# Main.net
KiCad netlist of a schematic drawn in Altium Designer
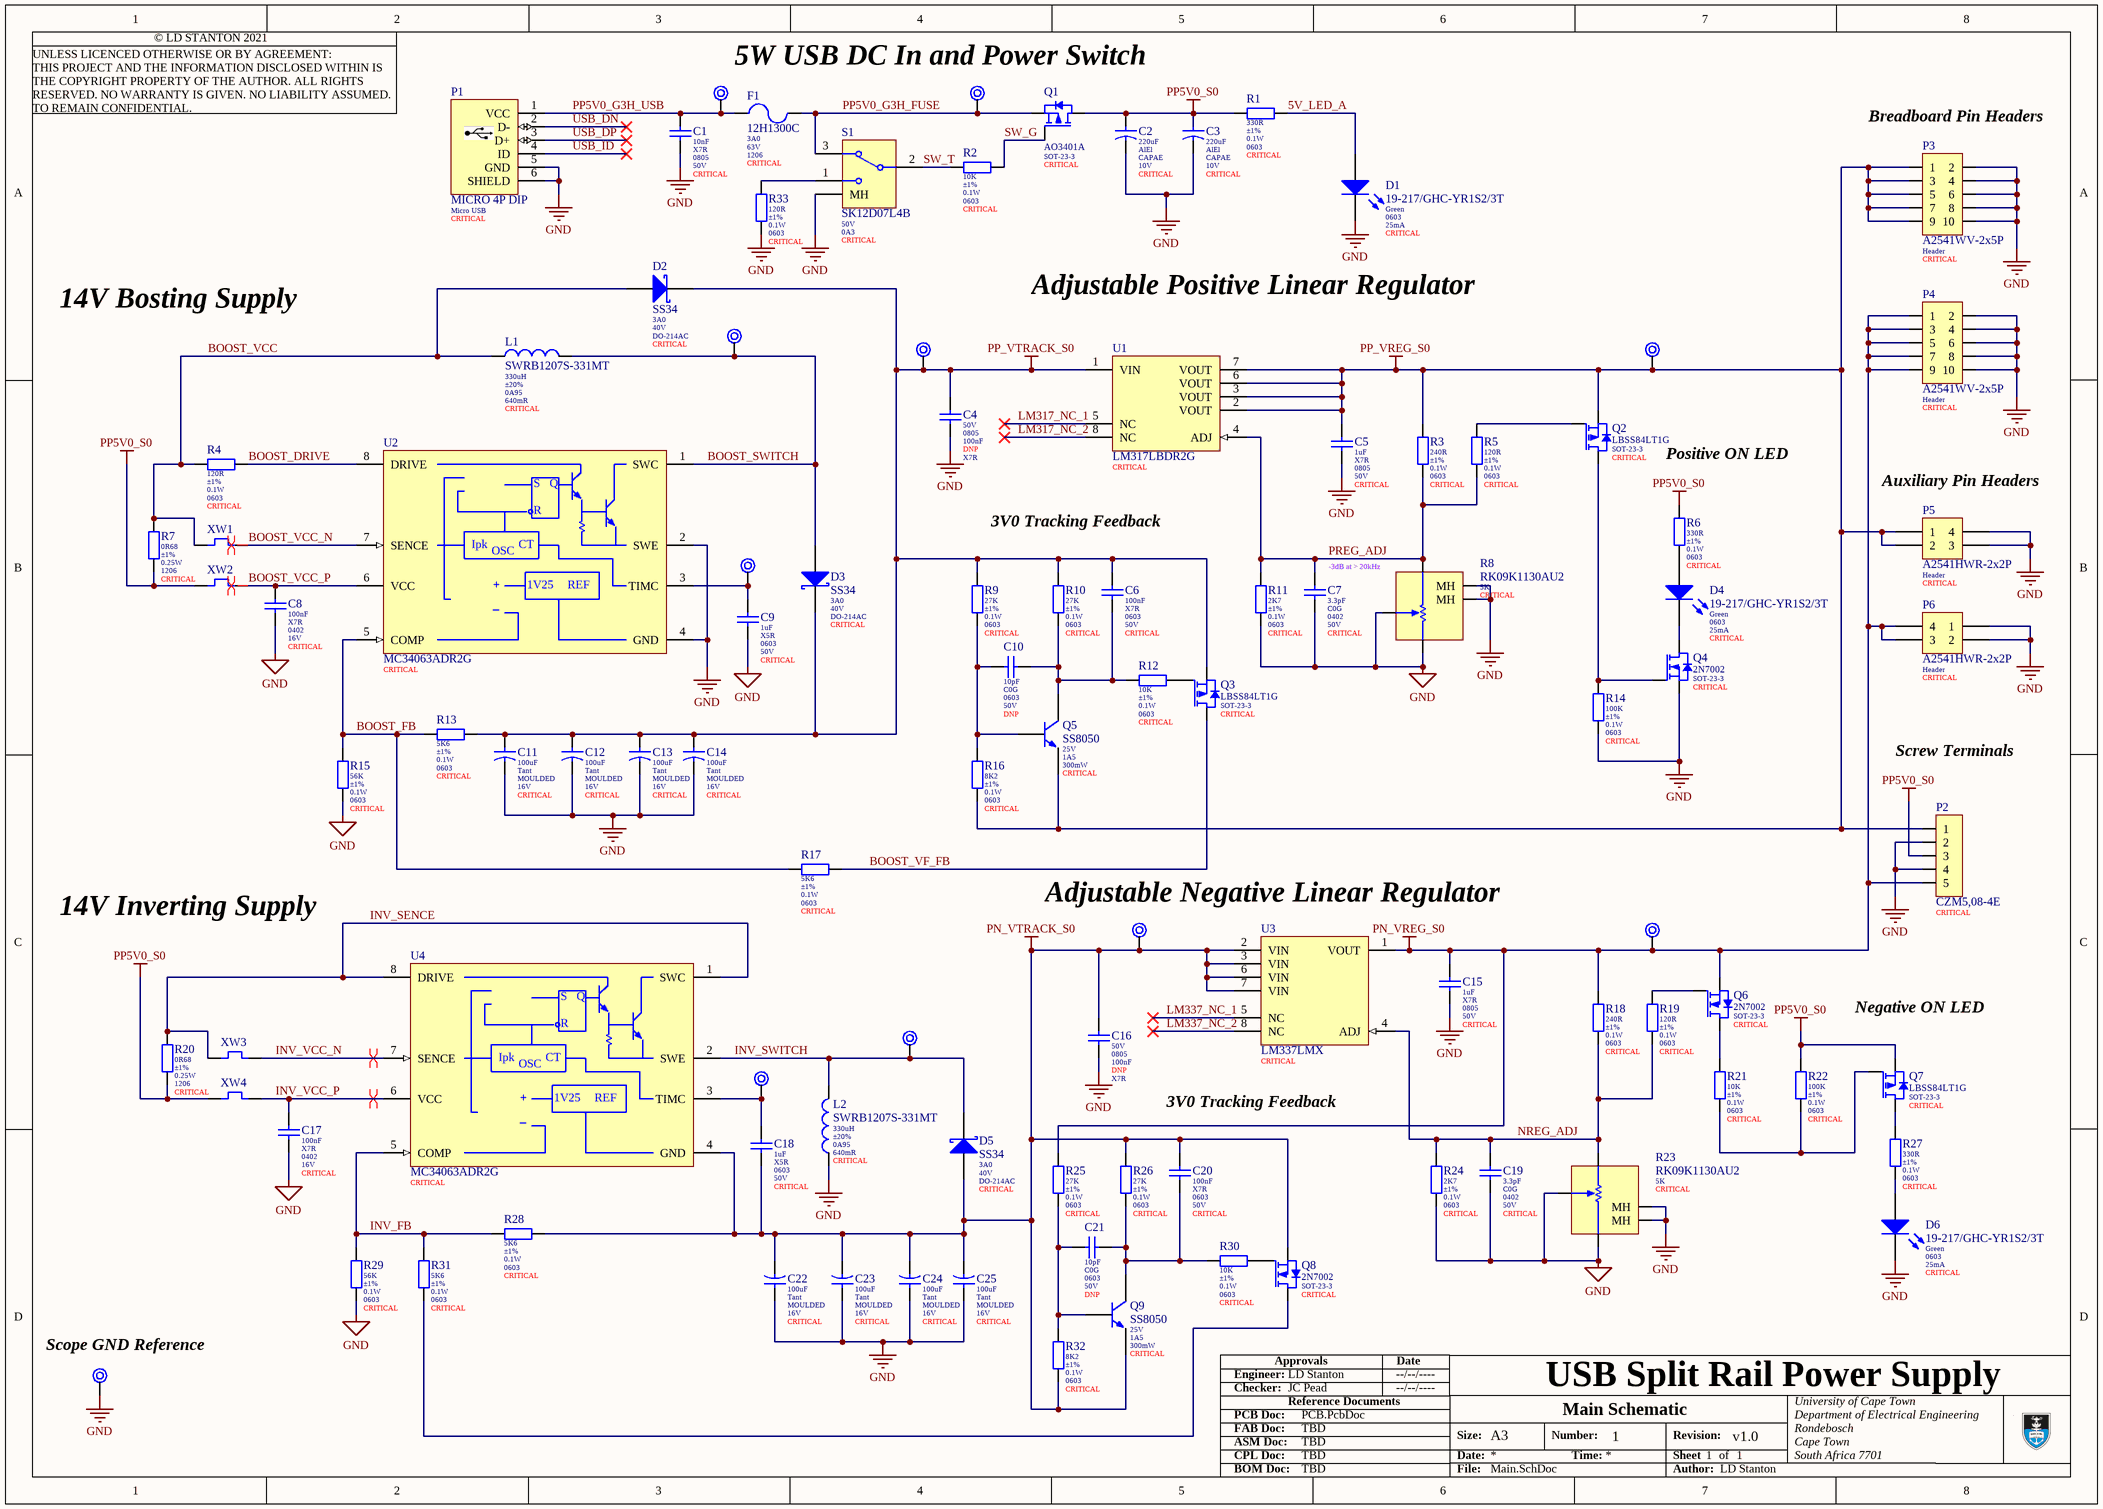
[diagram p0: Main.SchDoc]

(export (version "E")
  (design (tool "Eeschema 10.0.6"))
  (components
    (comp (ref "C1")
      (value "10nF")
      (footprint "0605_065_A_N")
      (description "MLCC 10nF 0805 50V X7R ±10%")
      (fields
        (field (name "TOLERANCE") "±10%")
        (field (name "LCSC PART NUMBER") "C1710")
        (field (name "DIELECTRIC") "X7R")
        (field (name "PACKAGE") "0805")
        (field (name "VOLTAGE") "50V")
        (field (name "POPULATE") "CRITICAL")
      )
      (libsource (lib "Samsung Capacitors") (part "MLCC 10nF 0805 50V X7R"))
    )
    (comp (ref "C2")
      (value "220uF")
      (footprint "CAPAE 6354")
      (description "Aluminium Electrolytic Capacitor 220uF CAPAE 10V ±20%")
      (fields
        (field (name "TOLERANCE") "±20%")
        (field (name "LCSC PART NUMBER") "C3345")
        (field (name "DIELECTRIC") "AlEl")
        (field (name "PACKAGE") "CAPAE")
        (field (name "VOLTAGE") "10V")
        (field (name "POPULATE") "CRITICAL")
      )
      (libsource (lib "JLCPCB Electrolytic Capacitors") (part "Cap AlEl 220uF 10V"))
    )
    (comp (ref "C3")
      (value "220uF")
      (footprint "CAPAE 6354")
      (description "Aluminium Electrolytic Capacitor 220uF CAPAE 10V ±20%")
      (fields
        (field (name "TOLERANCE") "±20%")
        (field (name "LCSC PART NUMBER") "C3345")
        (field (name "DIELECTRIC") "AlEl")
        (field (name "PACKAGE") "CAPAE")
        (field (name "VOLTAGE") "10V")
        (field (name "POPULATE") "CRITICAL")
      )
      (libsource (lib "JLCPCB Electrolytic Capacitors") (part "Cap AlEl 220uF 10V"))
    )
    (comp (ref "C4")
      (value "100nF")
      (footprint "0805")
      (description "MLCC 100nF 50V 0805 X7R ±10%")
      (fields
        (field (name "TOLERANCE") "±10%")
        (field (name "LCSC PART NUMBER") "C49678")
        (field (name "VOLTAGE") "50V")
        (field (name "PACKAGE") "0805")
        (field (name "POPULATE") "DNP")
        (field (name "DIELECTRIC") "X7R")
      )
      (libsource (lib "Yageo Capacitors") (part "MLCC 100nF 50V 0805 X7R"))
    )
    (comp (ref "C5")
      (value "1uF")
      (footprint "0805_125_F_N")
      (description "MLCC 1uF 0805 50V X7R ±10%")
      (fields
        (field (name "TOLERANCE") "±10%")
        (field (name "LCSC PART NUMBER") "C15849")
        (field (name "DIELECTRIC") "X7R")
        (field (name "PACKAGE") "0805")
        (field (name "VOLTAGE") "50V")
        (field (name "POPULATE") "CRITICAL")
      )
      (libsource (lib "Samsung Capacitors") (part "MLCC 1uF 0805 50V X7R"))
    )
    (comp (ref "C6")
      (value "100nF")
      (footprint "0603")
      (description "MLCC 100nF 50V 0603 X7R ±10%")
      (fields
        (field (name "TOLERANCE") "±10%")
        (field (name "LCSC PART NUMBER") "C14663")
        (field (name "DIELECTRIC") "X7R")
        (field (name "PACKAGE") "0603")
        (field (name "VOLTAGE") "50V")
        (field (name "POPULATE") "CRITICAL")
      )
      (libsource (lib "Yageo Capacitors") (part "MLCC 100nF 50V 0603 X7R"))
    )
    (comp (ref "C7")
      (value "3.3pF")
      (footprint "0402_050")
      (description "MLCC 3.3pF 0402 50V C0G ±0.25pF")
      (fields
        (field (name "TOLERANCE") "±0.25pF")
        (field (name "LCSC PART NUMBER") "C1565")
        (field (name "DIELECTRIC") "C0G")
        (field (name "PACKAGE") "0402")
        (field (name "VOLTAGE") "50V")
        (field (name "POPULATE") "CRITICAL")
      )
      (libsource (lib "Guangdong Capacitors") (part "MLCC 3.3pF 0402 50V C0G"))
    )
    (comp (ref "C8")
      (value "100nF")
      (footprint "0402_050_5_N")
      (description "MLCC 100nF 0402 16V X7R ±10%")
      (fields
        (field (name "TOLERANCE") "±10%")
        (field (name "LCSC PART NUMBER") "C1525")
        (field (name "DIELECTRIC") "X7R")
        (field (name "PACKAGE") "0402")
        (field (name "VOLTAGE") "16V")
        (field (name "POPULATE") "CRITICAL")
      )
      (libsource (lib "Samsung Capacitors") (part "MLCC 100nF 0402 16V X7R"))
    )
    (comp (ref "C9")
      (value "1uF")
      (footprint "0603_080_8_N")
      (description "MLCC 1uF 0603 50V X5R ±10%")
      (fields
        (field (name "TOLERANCE") "±10%")
        (field (name "LCSC PART NUMBER") "C15849")
        (field (name "DIELECTRIC") "X5R")
        (field (name "PACKAGE") "0603")
        (field (name "VOLTAGE") "50V")
        (field (name "POPULATE") "CRITICAL")
      )
      (libsource (lib "Samsung Capacitors") (part "MLCC 1uF 0603 50V X5R"))
    )
    (comp (ref "C10")
      (value "10pF")
      (footprint "0603_080_8_N")
      (description "MLCC 10pF 0603 C0G ±0.1pF")
      (fields
        (field (name "TOLERANCE") "±0.1pF")
        (field (name "LCSC PART NUMBER") "C1634")
        (field (name "DIELECTRIC") "C0G")
        (field (name "PACKAGE") "0603")
        (field (name "VOLTAGE") "50V")
        (field (name "POPULATE") "DNP")
      )
      (libsource (lib "Samsung Capacitors") (part "MLCC 10pF 0603 50V C0G"))
    )
    (comp (ref "C11")
      (value "100uF")
      (footprint "Case D")
      (description "Tantalum Capacitor 100uF 16V ±20%")
      (fields
        (field (name "TOLERANCE") "±20%")
        (field (name "LCSC PART NUMBER") "C129696")
        (field (name "DIELECTRIC") "Tant")
        (field (name "PACKAGE") "MOULDED")
        (field (name "VOLTAGE") "16V")
        (field (name "POPULATE") "CRITICAL")
      )
      (libsource (lib "Tantalums Vishay") (part "Cap Tant 100uF 16V"))
    )
    (comp (ref "C12")
      (value "100uF")
      (footprint "Case D")
      (description "Tantalum Capacitor 100uF 16V ±20%")
      (fields
        (field (name "TOLERANCE") "±20%")
        (field (name "LCSC PART NUMBER") "C129696")
        (field (name "DIELECTRIC") "Tant")
        (field (name "PACKAGE") "MOULDED")
        (field (name "VOLTAGE") "16V")
        (field (name "POPULATE") "CRITICAL")
      )
      (libsource (lib "Tantalums Vishay") (part "Cap Tant 100uF 16V"))
    )
    (comp (ref "C13")
      (value "100uF")
      (footprint "Case D")
      (description "Tantalum Capacitor 100uF 16V ±20%")
      (fields
        (field (name "TOLERANCE") "±20%")
        (field (name "LCSC PART NUMBER") "C129696")
        (field (name "DIELECTRIC") "Tant")
        (field (name "PACKAGE") "MOULDED")
        (field (name "VOLTAGE") "16V")
        (field (name "POPULATE") "CRITICAL")
      )
      (libsource (lib "Tantalums Vishay") (part "Cap Tant 100uF 16V"))
    )
    (comp (ref "C14")
      (value "100uF")
      (footprint "Case D")
      (description "Tantalum Capacitor 100uF 16V ±20%")
      (fields
        (field (name "TOLERANCE") "±20%")
        (field (name "LCSC PART NUMBER") "C129696")
        (field (name "DIELECTRIC") "Tant")
        (field (name "PACKAGE") "MOULDED")
        (field (name "VOLTAGE") "16V")
        (field (name "POPULATE") "CRITICAL")
      )
      (libsource (lib "Tantalums Vishay") (part "Cap Tant 100uF 16V"))
    )
    (comp (ref "C15")
      (value "1uF")
      (footprint "0805_125_F_N")
      (description "MLCC 1uF 0805 50V X7R ±10%")
      (fields
        (field (name "TOLERANCE") "±10%")
        (field (name "LCSC PART NUMBER") "C15849")
        (field (name "DIELECTRIC") "X7R")
        (field (name "PACKAGE") "0805")
        (field (name "VOLTAGE") "50V")
        (field (name "POPULATE") "CRITICAL")
      )
      (libsource (lib "Samsung Capacitors") (part "MLCC 1uF 0805 50V X7R"))
    )
    (comp (ref "C16")
      (value "100nF")
      (footprint "0805")
      (description "MLCC 100nF 50V 0805 X7R ±10%")
      (fields
        (field (name "TOLERANCE") "±10%")
        (field (name "LCSC PART NUMBER") "C49678")
        (field (name "VOLTAGE") "50V")
        (field (name "PACKAGE") "0805")
        (field (name "POPULATE") "DNP")
        (field (name "DIELECTRIC") "X7R")
      )
      (libsource (lib "Yageo Capacitors") (part "MLCC 100nF 50V 0805 X7R"))
    )
    (comp (ref "C17")
      (value "100nF")
      (footprint "0402_050_5_N")
      (description "MLCC 100nF 0402 16V X7R ±10%")
      (fields
        (field (name "TOLERANCE") "±10%")
        (field (name "LCSC PART NUMBER") "C1525")
        (field (name "DIELECTRIC") "X7R")
        (field (name "PACKAGE") "0402")
        (field (name "VOLTAGE") "16V")
        (field (name "POPULATE") "CRITICAL")
      )
      (libsource (lib "Samsung Capacitors") (part "MLCC 100nF 0402 16V X7R"))
    )
    (comp (ref "C18")
      (value "1uF")
      (footprint "0603_080_8_N")
      (description "MLCC 1uF 0603 50V X5R ±10%")
      (fields
        (field (name "TOLERANCE") "±10%")
        (field (name "LCSC PART NUMBER") "C15849")
        (field (name "DIELECTRIC") "X5R")
        (field (name "PACKAGE") "0603")
        (field (name "VOLTAGE") "50V")
        (field (name "POPULATE") "CRITICAL")
      )
      (libsource (lib "Samsung Capacitors") (part "MLCC 1uF 0603 50V X5R"))
    )
    (comp (ref "C19")
      (value "3.3pF")
      (footprint "0402_050")
      (description "MLCC 3.3pF 0402 50V C0G ±0.25pF")
      (fields
        (field (name "TOLERANCE") "±0.25pF")
        (field (name "LCSC PART NUMBER") "C1565")
        (field (name "DIELECTRIC") "C0G")
        (field (name "PACKAGE") "0402")
        (field (name "VOLTAGE") "50V")
        (field (name "POPULATE") "CRITICAL")
      )
      (libsource (lib "Guangdong Capacitors") (part "MLCC 3.3pF 0402 50V C0G"))
    )
    (comp (ref "C20")
      (value "100nF")
      (footprint "0603")
      (description "MLCC 100nF 50V 0603 X7R ±10%")
      (fields
        (field (name "TOLERANCE") "±10%")
        (field (name "LCSC PART NUMBER") "C14663")
        (field (name "DIELECTRIC") "X7R")
        (field (name "PACKAGE") "0603")
        (field (name "VOLTAGE") "50V")
        (field (name "POPULATE") "CRITICAL")
      )
      (libsource (lib "Yageo Capacitors") (part "MLCC 100nF 50V 0603 X7R"))
    )
    (comp (ref "C21")
      (value "10pF")
      (footprint "0603_080_8_N")
      (description "MLCC 10pF 0603 C0G ±0.1pF")
      (fields
        (field (name "TOLERANCE") "±0.1pF")
        (field (name "LCSC PART NUMBER") "C1634")
        (field (name "DIELECTRIC") "C0G")
        (field (name "PACKAGE") "0603")
        (field (name "VOLTAGE") "50V")
        (field (name "POPULATE") "DNP")
      )
      (libsource (lib "Samsung Capacitors") (part "MLCC 10pF 0603 50V C0G"))
    )
    (comp (ref "C22")
      (value "100uF")
      (footprint "Case D")
      (description "Tantalum Capacitor 100uF 16V ±20%")
      (fields
        (field (name "TOLERANCE") "±20%")
        (field (name "LCSC PART NUMBER") "C129696")
        (field (name "DIELECTRIC") "Tant")
        (field (name "PACKAGE") "MOULDED")
        (field (name "VOLTAGE") "16V")
        (field (name "POPULATE") "CRITICAL")
      )
      (libsource (lib "Tantalums Vishay") (part "Cap Tant 100uF 16V"))
    )
    (comp (ref "C23")
      (value "100uF")
      (footprint "Case D")
      (description "Tantalum Capacitor 100uF 16V ±20%")
      (fields
        (field (name "TOLERANCE") "±20%")
        (field (name "LCSC PART NUMBER") "C129696")
        (field (name "DIELECTRIC") "Tant")
        (field (name "PACKAGE") "MOULDED")
        (field (name "VOLTAGE") "16V")
        (field (name "POPULATE") "CRITICAL")
      )
      (libsource (lib "Tantalums Vishay") (part "Cap Tant 100uF 16V"))
    )
    (comp (ref "C24")
      (value "100uF")
      (footprint "Case D")
      (description "Tantalum Capacitor 100uF 16V ±20%")
      (fields
        (field (name "TOLERANCE") "±20%")
        (field (name "LCSC PART NUMBER") "C129696")
        (field (name "DIELECTRIC") "Tant")
        (field (name "PACKAGE") "MOULDED")
        (field (name "VOLTAGE") "16V")
        (field (name "POPULATE") "CRITICAL")
      )
      (libsource (lib "Tantalums Vishay") (part "Cap Tant 100uF 16V"))
    )
    (comp (ref "C25")
      (value "100uF")
      (footprint "Case D")
      (description "Tantalum Capacitor 100uF 16V ±20%")
      (fields
        (field (name "TOLERANCE") "±20%")
        (field (name "LCSC PART NUMBER") "C129696")
        (field (name "DIELECTRIC") "Tant")
        (field (name "PACKAGE") "MOULDED")
        (field (name "VOLTAGE") "16V")
        (field (name "POPULATE") "CRITICAL")
      )
      (libsource (lib "Tantalums Vishay") (part "Cap Tant 100uF 16V"))
    )
    (comp (ref "D1")
      (value "19-217/GHC-YR1S2/3T")
      (footprint "LED 0603")
      (description "LED 0603 SMT Green")
      (fields
        (field (name "LCSC PART NUMBER") "C72043")
        (field (name "COLOUR") "Green")
        (field (name "PACKAGE") "0603")
        (field (name "CURRENT") "25mA")
        (field (name "PLACEMENT") "CRITICAL")
      )
      (libsource (lib "JLCPCB LEDs") (part "LED 0603 Green"))
    )
    (comp (ref "D2")
      (value "SS34")
      (footprint "DO-214AC")
      (description "Schottky Barrier Diode 40V 3A0 550mV")
      (fields
        (field (name "LCSC PART NUMBER") "C8678")
        (field (name "MANUFACTURER") "MDD")
        (field (name "DC FORWARD CURENT") "3A0")
        (field (name "DC REVERSE BLOCKING") "40V")
        (field (name "PACKAGE") "DO-214AC")
        (field (name "PLACEMENT") "CRITICAL")
      )
      (libsource (lib "Schottky Barrier Diodes") (part "SS34"))
    )
    (comp (ref "D3")
      (value "SS34")
      (footprint "DO-214AC")
      (description "Schottky Barrier Diode 40V 3A0 550mV")
      (fields
        (field (name "LCSC PART NUMBER") "C8678")
        (field (name "MANUFACTURER") "MDD")
        (field (name "DC FORWARD CURENT") "3A0")
        (field (name "DC REVERSE BLOCKING") "40V")
        (field (name "PACKAGE") "DO-214AC")
        (field (name "PLACEMENT") "CRITICAL")
      )
      (libsource (lib "Schottky Barrier Diodes") (part "SS34"))
    )
    (comp (ref "D4")
      (value "19-217/GHC-YR1S2/3T")
      (footprint "LED 0603")
      (description "LED 0603 SMT Green")
      (fields
        (field (name "LCSC PART NUMBER") "C72043")
        (field (name "COLOUR") "Green")
        (field (name "PACKAGE") "0603")
        (field (name "CURRENT") "25mA")
        (field (name "PLACEMENT") "CRITICAL")
      )
      (libsource (lib "JLCPCB LEDs") (part "LED 0603 Green"))
    )
    (comp (ref "D5")
      (value "SS34")
      (footprint "DO-214AC")
      (description "Schottky Barrier Diode 40V 3A0 550mV")
      (fields
        (field (name "LCSC PART NUMBER") "C8678")
        (field (name "MANUFACTURER") "MDD")
        (field (name "DC FORWARD CURENT") "3A0")
        (field (name "DC REVERSE BLOCKING") "40V")
        (field (name "PACKAGE") "DO-214AC")
        (field (name "PLACEMENT") "CRITICAL")
      )
      (libsource (lib "Schottky Barrier Diodes") (part "SS34"))
    )
    (comp (ref "D6")
      (value "19-217/GHC-YR1S2/3T")
      (footprint "LED 0603")
      (description "LED 0603 SMT Green")
      (fields
        (field (name "LCSC PART NUMBER") "C72043")
        (field (name "COLOUR") "Green")
        (field (name "PACKAGE") "0603")
        (field (name "CURRENT") "25mA")
        (field (name "PLACEMENT") "CRITICAL")
      )
      (libsource (lib "JLCPCB LEDs") (part "LED 0603 Green"))
    )
    (comp (ref "F1")
      (value "12H1300C")
      (footprint "1206_060")
      (description "Fuse SMD Slow Blow 3A 63VAC 1206")
      (fields
        (field (name "LCSC PART NUMBER") "C182445")
        (field (name "CURRENT") "3A0")
        (field (name "VOLTAGE") "63V")
        (field (name "PACKAGE") "1206")
        (field (name "PLACEMENT") "CRITICAL")
      )
      (libsource (lib "Fuses") (part "Fuse 3A Slow 1206"))
    )
    (comp (ref "L1")
      (value "SWRB1207S-331MT")
      (footprint "SWRB1207S")
      (description "Inductor 330uH ±20% 0A95 640mR Moulded SMD 12.5x12.5x8.0mm")
      (fields
        (field (name "LCSC PART NUMBER") "C169381")
        (field (name "MANUFACTURER") "Sunlord")
        (field (name "ALTIUM_VALUE") "330uH")
        (field (name "TOLERANCE") "±20%")
        (field (name "RATED CURRENT") "0A95")
        (field (name "DC RESISTANCE") "640mR")
        (field (name "POPULATE") "CRITICAL")
      )
      (libsource (lib "JLCPCB Inductors") (part "Inductor 330uH ±20% 0A95"))
    )
    (comp (ref "L2")
      (value "SWRB1207S-331MT")
      (footprint "SWRB1207S")
      (description "Inductor 330uH ±20% 0A95 640mR Moulded SMD 12.5x12.5x8.0mm")
      (fields
        (field (name "LCSC PART NUMBER") "C169381")
        (field (name "MANUFACTURER") "Sunlord")
        (field (name "ALTIUM_VALUE") "330uH")
        (field (name "TOLERANCE") "±20%")
        (field (name "RATED CURRENT") "0A95")
        (field (name "DC RESISTANCE") "640mR")
        (field (name "POPULATE") "CRITICAL")
      )
      (libsource (lib "JLCPCB Inductors") (part "Inductor 330uH ±20% 0A95"))
    )
    (comp (ref "P1")
      (value "MICRO 4P DIP")
      (footprint "MICRO 4P DIP")
      (description "Micro USB Connector SMT with TH Mounts")
      (fields
        (field (name "LCSC PART NUMBER") "C456008")
        (field (name "USB CONNECTOR TYPE") "Micro USB")
        (field (name "PLACEMENT") "CRITICAL")
      )
      (libsource (lib "USB Connectors") (part "MICRO 4P DIP"))
    )
    (comp (ref "P2")
      (value "CZM5,08-4E")
      (footprint "Screw Down 5")
      (description "Screw Down Terminal 5 Way 5.08mm Pitch")
      (fields (field (name "PLACEMENT") "CRITICAL"))
      (libsource (lib "Connectors") (part "Screw Down 5 Way 5.08mm"))
    )
    (comp (ref "P3")
      (value "A2541WV-2x5P")
      (footprint "Pin Header 10 2 Vertical Male")
      (description "Pin Header 10 Way Double Row Vertical Angle")
      (fields
        (field (name "TYPE") "Header")
        (field (name "PLACEMENT") "CRITICAL")
        (field (name "LCSC PART NUMBER") "C225520")
      )
      (libsource (lib "JLCPCB Pin Headers") (part "Pin Header 10 2 Male Vertical"))
    )
    (comp (ref "P4")
      (value "A2541WV-2x5P")
      (footprint "Pin Header 10 2 Vertical Male")
      (description "Pin Header 10 Way Double Row Vertical Angle")
      (fields
        (field (name "TYPE") "Header")
        (field (name "PLACEMENT") "CRITICAL")
        (field (name "LCSC PART NUMBER") "C225520")
      )
      (libsource (lib "JLCPCB Pin Headers") (part "Pin Header 10 2 Male Vertical"))
    )
    (comp (ref "P5")
      (value "A2541HWR-2x2P")
      (footprint "Pin Header 4 2 Right Female")
      (description "Pin Header 4 Way Double Row Female Right Angle")
      (fields (field (name "TYPE") "Header") (field (name "PLACEMENT") "CRITICAL"))
      (libsource (lib "") (part "Pin Header 4 2 Female Right_1"))
    )
    (comp (ref "P6")
      (value "A2541HWR-2x2P")
      (footprint "Pin Header 4 2 Right Female")
      (description "Pin Header 4 Way Double Row Female Right Angle")
      (fields (field (name "TYPE") "Header") (field (name "PLACEMENT") "CRITICAL"))
      (libsource (lib "JLCPCB Pin Headers") (part "Pin Header 4 2 Female Right"))
    )
    (comp (ref "Q1")
      (value "AO3401A")
      (footprint "SOT-23-3 (2N7002)")
      (description "MOSFET Trench 4A0 30V 85mR ±12V P-Channel Enhancement AOS SOT-22-3L")
      (fields
        (field (name "POWER") "0.9W")
        (field (name "LCSC PART NUMBER") "C20917")
        (field (name "PACKAGE") "SOT-23-3")
        (field (name "PLACEMENT") "CRITICAL")
      )
      (libsource (lib "JLCPCB Transistors") (part "AO3401A"))
    )
    (comp (ref "Q2")
      (value "LBSS84LT1G")
      (footprint "SOT-23-3 (2N7002)")
      (description "Small Signal MOSFET, 130 mA, 50 V, P-Channel, Enhancement, LRC SOT-23-3")
      (fields
        (field (name "POWER") "0.225W")
        (field (name "LCSC PART NUMBER") "C8492")
        (field (name "PACKAGE") "SOT-23-3")
        (field (name "PLACEMENT") "CRITICAL")
      )
      (libsource (lib "JLCPCB Transistors") (part "LBSS84LT1G"))
    )
    (comp (ref "Q3")
      (value "LBSS84LT1G")
      (footprint "SOT-23-3 (2N7002)")
      (description "Small Signal MOSFET, 130 mA, 50 V, P-Channel, Enhancement, LRC SOT-23-3")
      (fields
        (field (name "POWER") "0.225W")
        (field (name "LCSC PART NUMBER") "C8492")
        (field (name "PACKAGE") "SOT-23-3")
        (field (name "PLACEMENT") "CRITICAL")
      )
      (libsource (lib "JLCPCB Transistors") (part "LBSS84LT1G"))
    )
    (comp (ref "Q4")
      (value "2N7002")
      (footprint "SOT-23-3 (2N7002)")
      (description "Small Signal MOSFET, 500 mA, 60 V, N-Channel, Enhancement, JCET SOT-23-3")
      (fields
        (field (name "POWER") "0.225W")
        (field (name "LCSC PART NUMBER") "C8545")
        (field (name "PACKAGE") "SOT-23-3")
        (field (name "PLACEMENT") "CRITICAL")
      )
      (libsource (lib "JLCPCB Transistors") (part "2N7002"))
    )
    (comp (ref "Q5")
      (value "SS8050")
      (footprint "SOT-23-3 Generic")
      (description "BJT NPN 1A5 25V SOT-23-3")
      (fields
        (field (name "MANUFACTURER") "Changjiang Electronics")
        (field (name "LCSC PART NUMBER") "C2150")
        (field (name "VCE") "25V")
        (field (name "COLLECTOR CURRENT") "1A5")
        (field (name "POWER") "300mW")
        (field (name "PLACEMENT") "CRITICAL")
      )
      (libsource (lib "JLCPCB Transistors") (part "SS8050"))
    )
    (comp (ref "Q6")
      (value "2N7002")
      (footprint "SOT-23-3 (2N7002)")
      (description "Small Signal MOSFET, 500 mA, 60 V, N-Channel, Enhancement, JCET SOT-23-3")
      (fields
        (field (name "POWER") "0.225W")
        (field (name "LCSC PART NUMBER") "C8545")
        (field (name "PACKAGE") "SOT-23-3")
        (field (name "PLACEMENT") "CRITICAL")
      )
      (libsource (lib "JLCPCB Transistors") (part "2N7002"))
    )
    (comp (ref "Q7")
      (value "LBSS84LT1G")
      (footprint "SOT-23-3 (2N7002)")
      (description "Small Signal MOSFET, 130 mA, 50 V, P-Channel, Enhancement, LRC SOT-23-3")
      (fields
        (field (name "POWER") "0.225W")
        (field (name "LCSC PART NUMBER") "C8492")
        (field (name "PACKAGE") "SOT-23-3")
        (field (name "PLACEMENT") "CRITICAL")
      )
      (libsource (lib "JLCPCB Transistors") (part "LBSS84LT1G"))
    )
    (comp (ref "Q8")
      (value "2N7002")
      (footprint "SOT-23-3 (2N7002)")
      (description "Small Signal MOSFET, 500 mA, 60 V, N-Channel, Enhancement, JCET SOT-23-3")
      (fields
        (field (name "POWER") "0.225W")
        (field (name "LCSC PART NUMBER") "C8545")
        (field (name "PACKAGE") "SOT-23-3")
        (field (name "PLACEMENT") "CRITICAL")
      )
      (libsource (lib "JLCPCB Transistors") (part "2N7002"))
    )
    (comp (ref "Q9")
      (value "SS8050")
      (footprint "SOT-23-3 Generic")
      (description "BJT NPN 1A5 25V SOT-23-3")
      (fields
        (field (name "MANUFACTURER") "Changjiang Electronics")
        (field (name "LCSC PART NUMBER") "C2150")
        (field (name "VCE") "25V")
        (field (name "COLLECTOR CURRENT") "1A5")
        (field (name "POWER") "300mW")
        (field (name "PLACEMENT") "CRITICAL")
      )
      (libsource (lib "JLCPCB Transistors") (part "SS8050"))
    )
    (comp (ref "R1")
      (value "330R")
      (footprint "0603")
      (description "Lead Free Thick Film Chip Resistor 0805 ±1%")
      (fields
        (field (name "LCSC PART NUMBER") "C23138")
        (field (name "TOLERANCE") "±1%")
        (field (name "POWER") "0.1W")
        (field (name "PACKAGE") "0603")
        (field (name "POPULATE") "CRITICAL")
        (field (name "Comment") "0603WAF3300T5E")
      )
      (libsource (lib "Uniroyal Resistors") (part "Res 330R 0603"))
    )
    (comp (ref "R2")
      (value "10K")
      (footprint "0603")
      (description "Lead Free Thick Film Chip Resistor 0603 ±1%")
      (fields
        (field (name "LCSC PART NUMBER") "C25804")
        (field (name "TOLERANCE") "±1%")
        (field (name "POWER") "0.1W")
        (field (name "PACKAGE") "0603")
        (field (name "POPULATE") "CRITICAL")
        (field (name "Comment") "0603WAF1002T5E")
      )
      (libsource (lib "Uniroyal Resistors") (part "Res 10K 0603"))
    )
    (comp (ref "R3")
      (value "240R")
      (footprint "0603")
      (description "Lead Free Thick Film Chip Resistor 0603 ±1%")
      (fields
        (field (name "LCSC PART NUMBER") "C23350")
        (field (name "TOLERANCE") "±1%")
        (field (name "POWER") "0.1W")
        (field (name "PACKAGE") "0603")
        (field (name "POPULATE") "CRITICAL")
        (field (name "Comment") "0603WAF2400T5E")
      )
      (libsource (lib "Uniroyal Resistors") (part "Res 240R 0603"))
    )
    (comp (ref "R4")
      (value "120R")
      (footprint "0603")
      (description "Lead Free Thick Film Chip Resistor 0603 ±1%")
      (fields
        (field (name "LCSC PART NUMBER") "C22787")
        (field (name "TOLERANCE") "±1%")
        (field (name "POWER") "0.1W")
        (field (name "PACKAGE") "0603")
        (field (name "POPULATE") "CRITICAL")
        (field (name "Comment") "0603WAF1200T5E")
      )
      (libsource (lib "Uniroyal Resistors") (part "Res 120R 0603"))
    )
    (comp (ref "R5")
      (value "120R")
      (footprint "0603")
      (description "Lead Free Thick Film Chip Resistor 0603 ±1%")
      (fields
        (field (name "LCSC PART NUMBER") "C22787")
        (field (name "TOLERANCE") "±1%")
        (field (name "POWER") "0.1W")
        (field (name "PACKAGE") "0603")
        (field (name "POPULATE") "CRITICAL")
        (field (name "Comment") "0603WAF1200T5E")
      )
      (libsource (lib "Uniroyal Resistors") (part "Res 120R 0603"))
    )
    (comp (ref "R6")
      (value "330R")
      (footprint "0603")
      (description "Lead Free Thick Film Chip Resistor 0805 ±1%")
      (fields
        (field (name "LCSC PART NUMBER") "C23138")
        (field (name "TOLERANCE") "±1%")
        (field (name "POWER") "0.1W")
        (field (name "PACKAGE") "0603")
        (field (name "POPULATE") "CRITICAL")
        (field (name "Comment") "0603WAF3300T5E")
      )
      (libsource (lib "Uniroyal Resistors") (part "Res 330R 0603"))
    )
    (comp (ref "R7")
      (value "0R68")
      (footprint "1206")
      (description "Lead Free Thick Film Chip Resistor 1206 ±1%")
      (fields
        (field (name "LCSC PART NUMBER") "C19108")
        (field (name "TOLERANCE") "±1%")
        (field (name "POWER") "0.25W")
        (field (name "PACKAGE") "1206")
        (field (name "POPULATE") "CRITICAL")
        (field (name "Comment") "1206W4F680LT5E")
      )
      (libsource (lib "Uniroyal Resistors") (part "Res 0R68 1206"))
    )
    (comp (ref "R8")
      (value "RK09K1130AU2")
      (footprint "RK09K113")
      (description "5K Potentiometer THT 9.8mm Diameter ±20% 20VDC")
      (fields
        (field (name "MANUFACTURER") "Alpsalpine")
        (field (name "RESISTANCE") "5K")
        (field (name "PLACEMENT") "CRITICAL")
        (field (name "LCSC PART NUMBER") "C388855")
      )
      (libsource (lib "Potentiometers") (part "Pot 5K THT 9.8mm"))
    )
    (comp (ref "R9")
      (value "27K")
      (footprint "0603")
      (description "Lead Free Thick Film Chip Resistor 0603 ±1%")
      (fields
        (field (name "LCSC PART NUMBER") "C22967")
        (field (name "TOLERANCE") "±1%")
        (field (name "POWER") "0.1W")
        (field (name "PACKAGE") "0603")
        (field (name "POPULATE") "CRITICAL")
        (field (name "Comment") "0603WAF2702T5E")
      )
      (libsource (lib "Uniroyal Resistors") (part "Res 27K 0603"))
    )
    (comp (ref "R10")
      (value "27K")
      (footprint "0603")
      (description "Lead Free Thick Film Chip Resistor 0603 ±1%")
      (fields
        (field (name "LCSC PART NUMBER") "C22967")
        (field (name "TOLERANCE") "±1%")
        (field (name "POWER") "0.1W")
        (field (name "PACKAGE") "0603")
        (field (name "POPULATE") "CRITICAL")
        (field (name "Comment") "0603WAF2702T5E")
      )
      (libsource (lib "Uniroyal Resistors") (part "Res 27K 0603"))
    )
    (comp (ref "R11")
      (value "2K7")
      (footprint "0603")
      (description "Lead Free Thick Film Chip Resistor 0603 ±1%")
      (fields
        (field (name "LCSC PART NUMBER") "C13167")
        (field (name "TOLERANCE") "±1%")
        (field (name "POWER") "0.1W")
        (field (name "PACKAGE") "0603")
        (field (name "POPULATE") "CRITICAL")
        (field (name "Comment") "0603WAF2701T5E")
      )
      (libsource (lib "Uniroyal Resistors") (part "Res 2K7 0603"))
    )
    (comp (ref "R12")
      (value "10K")
      (footprint "0603")
      (description "Lead Free Thick Film Chip Resistor 0603 ±1%")
      (fields
        (field (name "LCSC PART NUMBER") "C25804")
        (field (name "TOLERANCE") "±1%")
        (field (name "POWER") "0.1W")
        (field (name "PACKAGE") "0603")
        (field (name "POPULATE") "CRITICAL")
        (field (name "Comment") "0603WAF1002T5E")
      )
      (libsource (lib "Uniroyal Resistors") (part "Res 10K 0603"))
    )
    (comp (ref "R13")
      (value "5K6")
      (footprint "0603")
      (description "Lead Free Thick Film Chip Resistor 0603 ±1%")
      (fields
        (field (name "LCSC PART NUMBER") "C23189")
        (field (name "TOLERANCE") "±1%")
        (field (name "POWER") "0.1W")
        (field (name "PACKAGE") "0603")
        (field (name "POPULATE") "CRITICAL")
        (field (name "Comment") "0603WAF5601T5E")
      )
      (libsource (lib "Uniroyal Resistors") (part "Res 5K6 0603"))
    )
    (comp (ref "R14")
      (value "100K")
      (footprint "0603")
      (description "Lead Free Thick Film Chip Resistor 0603 ±1%")
      (fields
        (field (name "LCSC PART NUMBER") "C25803")
        (field (name "TOLERANCE") "±1%")
        (field (name "POWER") "0.1W")
        (field (name "PACKAGE") "0603")
        (field (name "POPULATE") "CRITICAL")
        (field (name "Comment") "0603WAF1003T5E")
      )
      (libsource (lib "Uniroyal Resistors") (part "Res 100K 0603"))
    )
    (comp (ref "R15")
      (value "56K")
      (footprint "0603")
      (description "Lead Free Thick Film Chip Resistor 0603 ±1%")
      (fields
        (field (name "LCSC PART NUMBER") "C23206")
        (field (name "TOLERANCE") "±1%")
        (field (name "POWER") "0.1W")
        (field (name "PACKAGE") "0603")
        (field (name "POPULATE") "CRITICAL")
        (field (name "Comment") "0603WAF5602T5E")
      )
      (libsource (lib "Uniroyal Resistors") (part "Res 56K 0603"))
    )
    (comp (ref "R16")
      (value "8K2")
      (footprint "0603")
      (description "Lead Free Thick Film Chip Resistor 0603 ±1%")
      (fields
        (field (name "LCSC PART NUMBER") "C25981")
        (field (name "TOLERANCE") "±1%")
        (field (name "POWER") "0.1W")
        (field (name "PACKAGE") "0603")
        (field (name "POPULATE") "CRITICAL")
        (field (name "Comment") "0603WAF8201T5E")
      )
      (libsource (lib "Uniroyal Resistors") (part "Res 8K2 0603"))
    )
    (comp (ref "R17")
      (value "5K6")
      (footprint "0603")
      (description "Lead Free Thick Film Chip Resistor 0603 ±1%")
      (fields
        (field (name "LCSC PART NUMBER") "C23189")
        (field (name "TOLERANCE") "±1%")
        (field (name "POWER") "0.1W")
        (field (name "PACKAGE") "0603")
        (field (name "POPULATE") "CRITICAL")
        (field (name "Comment") "0603WAF5601T5E")
      )
      (libsource (lib "Uniroyal Resistors") (part "Res 5K6 0603"))
    )
    (comp (ref "R18")
      (value "240R")
      (footprint "0603")
      (description "Lead Free Thick Film Chip Resistor 0603 ±1%")
      (fields
        (field (name "LCSC PART NUMBER") "C23350")
        (field (name "TOLERANCE") "±1%")
        (field (name "POWER") "0.1W")
        (field (name "PACKAGE") "0603")
        (field (name "POPULATE") "CRITICAL")
        (field (name "Comment") "0603WAF2400T5E")
      )
      (libsource (lib "Uniroyal Resistors") (part "Res 240R 0603"))
    )
    (comp (ref "R19")
      (value "120R")
      (footprint "0603")
      (description "Lead Free Thick Film Chip Resistor 0603 ±1%")
      (fields
        (field (name "LCSC PART NUMBER") "C22787")
        (field (name "TOLERANCE") "±1%")
        (field (name "POWER") "0.1W")
        (field (name "PACKAGE") "0603")
        (field (name "POPULATE") "CRITICAL")
        (field (name "Comment") "0603WAF1200T5E")
      )
      (libsource (lib "Uniroyal Resistors") (part "Res 120R 0603"))
    )
    (comp (ref "R20")
      (value "0R68")
      (footprint "1206")
      (description "Lead Free Thick Film Chip Resistor 1206 ±1%")
      (fields
        (field (name "LCSC PART NUMBER") "C19108")
        (field (name "TOLERANCE") "±1%")
        (field (name "POWER") "0.25W")
        (field (name "PACKAGE") "1206")
        (field (name "POPULATE") "CRITICAL")
        (field (name "Comment") "1206W4F680LT5E")
      )
      (libsource (lib "Uniroyal Resistors") (part "Res 0R68 1206"))
    )
    (comp (ref "R21")
      (value "10K")
      (footprint "0603")
      (description "Lead Free Thick Film Chip Resistor 0603 ±1%")
      (fields
        (field (name "LCSC PART NUMBER") "C25804")
        (field (name "TOLERANCE") "±1%")
        (field (name "POWER") "0.1W")
        (field (name "PACKAGE") "0603")
        (field (name "POPULATE") "CRITICAL")
        (field (name "Comment") "0603WAF1002T5E")
      )
      (libsource (lib "Uniroyal Resistors") (part "Res 10K 0603"))
    )
    (comp (ref "R22")
      (value "100K")
      (footprint "0603")
      (description "Lead Free Thick Film Chip Resistor 0603 ±1%")
      (fields
        (field (name "LCSC PART NUMBER") "C25803")
        (field (name "TOLERANCE") "±1%")
        (field (name "POWER") "0.1W")
        (field (name "PACKAGE") "0603")
        (field (name "POPULATE") "CRITICAL")
        (field (name "Comment") "0603WAF1003T5E")
      )
      (libsource (lib "Uniroyal Resistors") (part "Res 100K 0603"))
    )
    (comp (ref "R23")
      (value "RK09K1130AU2")
      (footprint "RK09K113")
      (description "5K Potentiometer THT 9.8mm Diameter ±20% 20VDC")
      (fields
        (field (name "MANUFACTURER") "Alpsalpine")
        (field (name "RESISTANCE") "5K")
        (field (name "PLACEMENT") "CRITICAL")
        (field (name "LCSC PART NUMBER") "C388855")
      )
      (libsource (lib "") (part "Pot 5K THT 9.8mm_1"))
    )
    (comp (ref "R24")
      (value "2K7")
      (footprint "0603")
      (description "Lead Free Thick Film Chip Resistor 0603 ±1%")
      (fields
        (field (name "LCSC PART NUMBER") "C13167")
        (field (name "TOLERANCE") "±1%")
        (field (name "POWER") "0.1W")
        (field (name "PACKAGE") "0603")
        (field (name "POPULATE") "CRITICAL")
        (field (name "Comment") "0603WAF2701T5E")
      )
      (libsource (lib "Uniroyal Resistors") (part "Res 2K7 0603"))
    )
    (comp (ref "R25")
      (value "27K")
      (footprint "0603")
      (description "Lead Free Thick Film Chip Resistor 0603 ±1%")
      (fields
        (field (name "LCSC PART NUMBER") "C22967")
        (field (name "TOLERANCE") "±1%")
        (field (name "POWER") "0.1W")
        (field (name "PACKAGE") "0603")
        (field (name "POPULATE") "CRITICAL")
        (field (name "Comment") "0603WAF2702T5E")
      )
      (libsource (lib "Uniroyal Resistors") (part "Res 27K 0603"))
    )
    (comp (ref "R26")
      (value "27K")
      (footprint "0603")
      (description "Lead Free Thick Film Chip Resistor 0603 ±1%")
      (fields
        (field (name "LCSC PART NUMBER") "C22967")
        (field (name "TOLERANCE") "±1%")
        (field (name "POWER") "0.1W")
        (field (name "PACKAGE") "0603")
        (field (name "POPULATE") "CRITICAL")
        (field (name "Comment") "0603WAF2702T5E")
      )
      (libsource (lib "Uniroyal Resistors") (part "Res 27K 0603"))
    )
    (comp (ref "R27")
      (value "330R")
      (footprint "0603")
      (description "Lead Free Thick Film Chip Resistor 0805 ±1%")
      (fields
        (field (name "LCSC PART NUMBER") "C23138")
        (field (name "TOLERANCE") "±1%")
        (field (name "POWER") "0.1W")
        (field (name "PACKAGE") "0603")
        (field (name "POPULATE") "CRITICAL")
        (field (name "Comment") "0603WAF3300T5E")
      )
      (libsource (lib "Uniroyal Resistors") (part "Res 330R 0603"))
    )
    (comp (ref "R28")
      (value "5K6")
      (footprint "0603")
      (description "Lead Free Thick Film Chip Resistor 0603 ±1%")
      (fields
        (field (name "LCSC PART NUMBER") "C23189")
        (field (name "TOLERANCE") "±1%")
        (field (name "POWER") "0.1W")
        (field (name "PACKAGE") "0603")
        (field (name "POPULATE") "CRITICAL")
        (field (name "Comment") "0603WAF5601T5E")
      )
      (libsource (lib "Uniroyal Resistors") (part "Res 5K6 0603"))
    )
    (comp (ref "R29")
      (value "56K")
      (footprint "0603")
      (description "Lead Free Thick Film Chip Resistor 0603 ±1%")
      (fields
        (field (name "LCSC PART NUMBER") "C23206")
        (field (name "TOLERANCE") "±1%")
        (field (name "POWER") "0.1W")
        (field (name "PACKAGE") "0603")
        (field (name "POPULATE") "CRITICAL")
        (field (name "Comment") "0603WAF5602T5E")
      )
      (libsource (lib "Uniroyal Resistors") (part "Res 56K 0603"))
    )
    (comp (ref "R30")
      (value "10K")
      (footprint "0603")
      (description "Lead Free Thick Film Chip Resistor 0603 ±1%")
      (fields
        (field (name "LCSC PART NUMBER") "C25804")
        (field (name "TOLERANCE") "±1%")
        (field (name "POWER") "0.1W")
        (field (name "PACKAGE") "0603")
        (field (name "POPULATE") "CRITICAL")
        (field (name "Comment") "0603WAF1002T5E")
      )
      (libsource (lib "Uniroyal Resistors") (part "Res 10K 0603"))
    )
    (comp (ref "R31")
      (value "5K6")
      (footprint "0603")
      (description "Lead Free Thick Film Chip Resistor 0603 ±1%")
      (fields
        (field (name "LCSC PART NUMBER") "C23189")
        (field (name "TOLERANCE") "±1%")
        (field (name "POWER") "0.1W")
        (field (name "PACKAGE") "0603")
        (field (name "POPULATE") "CRITICAL")
        (field (name "Comment") "0603WAF5601T5E")
      )
      (libsource (lib "Uniroyal Resistors") (part "Res 5K6 0603"))
    )
    (comp (ref "R32")
      (value "8K2")
      (footprint "0603")
      (description "Lead Free Thick Film Chip Resistor 0603 ±1%")
      (fields
        (field (name "LCSC PART NUMBER") "C25981")
        (field (name "TOLERANCE") "±1%")
        (field (name "POWER") "0.1W")
        (field (name "PACKAGE") "0603")
        (field (name "POPULATE") "CRITICAL")
        (field (name "Comment") "0603WAF8201T5E")
      )
      (libsource (lib "Uniroyal Resistors") (part "Res 8K2 0603"))
    )
    (comp (ref "R33")
      (value "120R")
      (footprint "0603")
      (description "Lead Free Thick Film Chip Resistor 0603 ±1%")
      (fields
        (field (name "LCSC PART NUMBER") "C22787")
        (field (name "TOLERANCE") "±1%")
        (field (name "POWER") "0.1W")
        (field (name "PACKAGE") "0603")
        (field (name "POPULATE") "CRITICAL")
        (field (name "Comment") "0603WAF1200T5E")
      )
      (libsource (lib "Uniroyal Resistors") (part "Res 120R 0603"))
    )
    (comp (ref "S1")
      (value "SK12D07L4B")
      (footprint "SK12D07L4B")
      (description "Switch Toggle Slider THT Right Angle 0A3 50V")
      (fields
        (field (name "VOLTAGE") "50V")
        (field (name "CURRENT") "0A3")
        (field (name "PLACEMENT") "CRITICAL")
        (field (name "LCSC PART NUMBER") "C480340")
      )
      (libsource (lib "Slide Switches") (part "SW Toggle Slide Right Angle 0A3 50V"))
    )
    (comp (ref "TP1")
      (value "Test Point")
      (footprint "Test Point 0.6")
      (description "Test Point. Multiple pad options.")
      (libsource (lib "Passives") (part "Test Point"))
    )
    (comp (ref "TP2")
      (value "Test Point")
      (footprint "Test Point 0.6")
      (description "Test Point. Multiple pad options.")
      (libsource (lib "Passives") (part "Test Point"))
    )
    (comp (ref "TP3")
      (value "Test Point")
      (footprint "Test Point 0.6")
      (description "Test Point. Multiple pad options.")
      (libsource (lib "Passives") (part "Test Point"))
    )
    (comp (ref "TP4")
      (value "Test Point")
      (footprint "Test Point 0.6")
      (description "Test Point. Multiple pad options.")
      (libsource (lib "Passives") (part "Test Point"))
    )
    (comp (ref "TP5")
      (value "Test Point")
      (footprint "Test Point 0.6")
      (description "Test Point. Multiple pad options.")
      (libsource (lib "Passives") (part "Test Point"))
    )
    (comp (ref "TP6")
      (value "Test Point")
      (footprint "Test Point 0.6")
      (description "Test Point. Multiple pad options.")
      (libsource (lib "Passives") (part "Test Point"))
    )
    (comp (ref "TP7")
      (value "Test Point")
      (footprint "Test Point 0.6")
      (description "Test Point. Multiple pad options.")
      (libsource (lib "Passives") (part "Test Point"))
    )
    (comp (ref "TP8")
      (value "Test Point")
      (footprint "Test Point 0.6")
      (description "Test Point. Multiple pad options.")
      (libsource (lib "Passives") (part "Test Point"))
    )
    (comp (ref "TP9")
      (value "Test Point")
      (footprint "Test Point 0.6")
      (description "Test Point. Multiple pad options.")
      (libsource (lib "Passives") (part "Test Point"))
    )
    (comp (ref "TP10")
      (value "Test Point")
      (footprint "Test Point 0.6")
      (description "Test Point. Multiple pad options.")
      (libsource (lib "Passives") (part "Test Point"))
    )
    (comp (ref "TP11")
      (value "Test Point")
      (footprint "Test Point 0.8 TH")
      (description "Test Point. Multiple pad options.")
      (libsource (lib "Passives") (part "Test Point"))
    )
    (comp (ref "U1")
      (value "LM317LBDR2G")
      (footprint "SOIC-8 NB")
      (description "100mA, 1V2 - 37V Adjustable Output, Positive Voltage Regulator")
      (fields
        (field (name "MANUFACTURER") "ON Semiconductor")
        (field (name "LCSC PART NUMBER") "C274645")
        (field (name "PLACEMENT") "CRITICAL")
      )
      (libsource (lib "Linear Regulators") (part "LM317LBDR2G"))
    )
    (comp (ref "U2")
      (value "MC34063ADR2G")
      (footprint "SOIC-8 NB")
      (description "1A5 Step-Up, Step-Down, Inverting Switching Reulator")
      (fields
        (field (name "MANUFACTURER") "ON Semi")
        (field (name "LCSC PART NUMBER") "C32078")
        (field (name "PLACEMENT") "CRITICAL")
      )
      (libsource (lib "Switching Regulators") (part "MC34063ADR2G"))
    )
    (comp (ref "U3")
      (value "LM337LMX")
      (footprint "SOIC-8 D (R-PDSO-G8)")
      (description "100mA, -1V2 to -37V Adjustable Negative Voltage Regulator")
      (fields
        (field (name "MANUFACTURER") "Texas Instruments")
        (field (name "LCSC PART NUMBER") "C7947")
        (field (name "PLACEMENT") "CRITICAL")
      )
      (libsource (lib "Linear Regulators") (part "LM337LMX"))
    )
    (comp (ref "U4")
      (value "MC34063ADR2G")
      (footprint "SOIC-8 NB")
      (description "1A5 Step-Up, Step-Down, Inverting Switching Reulator")
      (fields
        (field (name "MANUFACTURER") "ON Semi")
        (field (name "LCSC PART NUMBER") "C32078")
        (field (name "PLACEMENT") "CRITICAL")
      )
      (libsource (lib "Switching Regulators") (part "MC34063ADR2G"))
    )
    (comp (ref "XW1")
      (value "Short 2 Nets")
      (footprint "Short 0.5mm 2 Net")
      (description "Net Tie 2 Nets")
      (libsource (lib "Passives") (part "Short 2 Nets"))
    )
    (comp (ref "XW2")
      (value "Short 2 Nets")
      (footprint "Short 0.5mm 2 Net")
      (description "Net Tie 2 Nets")
      (libsource (lib "Passives") (part "Short 2 Nets"))
    )
    (comp (ref "XW3")
      (value "Short 2 Nets")
      (footprint "Short 0.5mm 2 Net")
      (description "Net Tie 2 Nets")
      (libsource (lib "Passives") (part "Short 2 Nets"))
    )
    (comp (ref "XW4")
      (value "Short 2 Nets")
      (footprint "Short 0.5mm 2 Net")
      (description "Net Tie 2 Nets")
      (libsource (lib "Passives") (part "Short 2 Nets"))
    )
  )
  (nets
    (net (code "1") (name "/5V_LED_A") (class "Default")
      (node (ref "D1") (pin "A") (pinfunction "A_A") (pintype "passive"))
      (node (ref "R1") (pin "2") (pinfunction "2_2") (pintype "passive"))
    )
    (net (code "2") (name "/BOOST_DRIVE") (class "Default")
      (node (ref "R4") (pin "2") (pinfunction "2_2") (pintype "passive"))
      (node (ref "U2") (pin "8") (pinfunction "DRIVE_8") (pintype "open_collector"))
    )
    (net (code "3") (name "/BOOST_FB") (class "Default")
      (node (ref "R13") (pin "1") (pinfunction "1_1") (pintype "passive"))
      (node (ref "R15") (pin "1") (pinfunction "1_1") (pintype "passive"))
      (node (ref "R17") (pin "1") (pinfunction "1_1") (pintype "passive"))
      (node (ref "U2") (pin "5") (pinfunction "COMP_5") (pintype "input"))
    )
    (net (code "4") (name "/BOOST_SWITCH") (class "Default")
      (node (ref "D3") (pin "2") (pinfunction "A_2") (pintype "passive"))
      (node (ref "L1") (pin "2") (pinfunction "2_2") (pintype "passive"))
      (node (ref "TP3") (pin "1") (pinfunction "1_1") (pintype "passive"))
      (node (ref "U2") (pin "1") (pinfunction "SWC_1") (pintype "open_collector"))
    )
    (net (code "5") (name "/BOOST_VCC") (class "Default")
      (node (ref "D2") (pin "2") (pinfunction "A_2") (pintype "passive"))
      (node (ref "L1") (pin "1") (pinfunction "1_1") (pintype "passive"))
      (node (ref "R4") (pin "1") (pinfunction "1_1") (pintype "passive"))
      (node (ref "R7") (pin "1") (pinfunction "1_1") (pintype "passive"))
      (node (ref "XW1") (pin "2") (pinfunction "2_2") (pintype "passive"))
    )
    (net (code "6") (name "/BOOST_VCC_N") (class "Default")
      (node (ref "U2") (pin "7") (pinfunction "SENCE_7") (pintype "input"))
      (node (ref "XW1") (pin "1") (pinfunction "1_1") (pintype "passive"))
    )
    (net (code "7") (name "/BOOST_VCC_P") (class "Default")
      (node (ref "C8") (pin "1") (pinfunction "1_1") (pintype "passive"))
      (node (ref "U2") (pin "6") (pinfunction "VCC_6") (pintype "tri_state"))
      (node (ref "XW2") (pin "1") (pinfunction "1_1") (pintype "passive"))
    )
    (net (code "8") (name "/BOOST_VF_FB") (class "Default")
      (node (ref "Q3") (pin "3") (pinfunction "D_3") (pintype "passive"))
      (node (ref "R17") (pin "2") (pinfunction "2_2") (pintype "passive"))
    )
    (net (code "9") (name "/INV_FB") (class "Default")
      (node (ref "R28") (pin "1") (pinfunction "1_1") (pintype "passive"))
      (node (ref "R29") (pin "1") (pinfunction "1_1") (pintype "passive"))
      (node (ref "R31") (pin "2") (pinfunction "2_2") (pintype "passive"))
      (node (ref "U4") (pin "5") (pinfunction "COMP_5") (pintype "input"))
    )
    (net (code "10") (name "/INV_SENCE") (class "Default")
      (node (ref "R20") (pin "1") (pinfunction "1_1") (pintype "passive"))
      (node (ref "U4") (pin "1") (pinfunction "SWC_1") (pintype "open_collector"))
      (node (ref "U4") (pin "8") (pinfunction "DRIVE_8") (pintype "open_collector"))
      (node (ref "XW3") (pin "2") (pinfunction "2_2") (pintype "passive"))
    )
    (net (code "11") (name "/INV_SWITCH") (class "Default")
      (node (ref "D5") (pin "1") (pinfunction "K_1") (pintype "passive"))
      (node (ref "L2") (pin "2") (pinfunction "2_2") (pintype "passive"))
      (node (ref "TP9") (pin "1") (pinfunction "1_1") (pintype "passive"))
      (node (ref "U4") (pin "2") (pinfunction "SWE_2") (pintype "passive"))
    )
    (net (code "12") (name "/INV_VCC_N") (class "Default")
      (node (ref "U4") (pin "7") (pinfunction "SENCE_7") (pintype "input"))
      (node (ref "XW3") (pin "1") (pinfunction "1_1") (pintype "passive"))
    )
    (net (code "13") (name "/INV_VCC_P") (class "Default")
      (node (ref "C17") (pin "1") (pinfunction "1_1") (pintype "passive"))
      (node (ref "U4") (pin "6") (pinfunction "VCC_6") (pintype "tri_state"))
      (node (ref "XW4") (pin "1") (pinfunction "1_1") (pintype "passive"))
    )
    (net (code "14") (name "/LM317_NC_1") (class "Default")
      (node (ref "U1") (pin "5") (pinfunction "NC_5") (pintype "passive+no_connect"))
    )
    (net (code "15") (name "/LM317_NC_2") (class "Default")
      (node (ref "U1") (pin "8") (pinfunction "NC_8") (pintype "passive+no_connect"))
    )
    (net (code "16") (name "/LM337_NC_1") (class "Default")
      (node (ref "U3") (pin "5") (pinfunction "NC_5") (pintype "passive+no_connect"))
    )
    (net (code "17") (name "/LM337_NC_2") (class "Default")
      (node (ref "U3") (pin "8") (pinfunction "NC_8") (pintype "passive+no_connect"))
    )
    (net (code "18") (name "/NREG_ADJ") (class "Default")
      (node (ref "C19") (pin "1") (pinfunction "1_1") (pintype "passive"))
      (node (ref "R18") (pin "2") (pinfunction "2_2") (pintype "passive"))
      (node (ref "R19") (pin "1") (pinfunction "1_1") (pintype "passive"))
      (node (ref "R23") (pin "1") (pinfunction "1_1") (pintype "passive"))
      (node (ref "R24") (pin "1") (pinfunction "1_1") (pintype "passive"))
      (node (ref "U3") (pin "4") (pinfunction "ADJ_4") (pintype "input"))
    )
    (net (code "19") (name "/PP5V0_G3H_FUSE") (class "Default")
      (node (ref "F1") (pin "2") (pinfunction "2_2") (pintype "passive"))
      (node (ref "Q1") (pin "2") (pinfunction "S_2") (pintype "passive"))
      (node (ref "S1") (pin "3") (pinfunction "3_3") (pintype "passive"))
      (node (ref "TP2") (pin "1") (pinfunction "1_1") (pintype "passive"))
    )
    (net (code "20") (name "/PP5V0_G3H_USB") (class "Default")
      (node (ref "C1") (pin "1") (pinfunction "1_1") (pintype "passive"))
      (node (ref "F1") (pin "1") (pinfunction "1_1") (pintype "passive"))
      (node (ref "P1") (pin "1") (pinfunction "VCC_1") (pintype "power_in"))
      (node (ref "TP1") (pin "1") (pinfunction "1_1") (pintype "passive"))
    )
    (net (code "21") (name "/PREG_ADJ") (class "Default")
      (node (ref "C7") (pin "1") (pinfunction "1_1") (pintype "passive"))
      (node (ref "R11") (pin "1") (pinfunction "1_1") (pintype "passive"))
      (node (ref "R3") (pin "2") (pinfunction "2_2") (pintype "passive"))
      (node (ref "R5") (pin "1") (pinfunction "1_1") (pintype "passive"))
      (node (ref "R8") (pin "3") (pinfunction "3_3") (pintype "passive"))
      (node (ref "U1") (pin "4") (pinfunction "ADJ_4") (pintype "input"))
    )
    (net (code "22") (name "/SW_G") (class "Default")
      (node (ref "Q1") (pin "1") (pinfunction "G_1") (pintype "passive"))
      (node (ref "R2") (pin "2") (pinfunction "2_2") (pintype "passive"))
    )
    (net (code "23") (name "/SW_T") (class "Default")
      (node (ref "R2") (pin "1") (pinfunction "1_1") (pintype "passive"))
      (node (ref "S1") (pin "2") (pinfunction "2_2") (pintype "passive"))
    )
    (net (code "24") (name "/USB_DN") (class "Default")
      (node (ref "P1") (pin "2") (pinfunction "D-_2") (pintype "bidirectional+no_connect"))
    )
    (net (code "25") (name "/USB_DP") (class "Default")
      (node (ref "P1") (pin "3") (pinfunction "D+_3") (pintype "bidirectional+no_connect"))
    )
    (net (code "26") (name "/USB_ID") (class "Default")
      (node (ref "P1") (pin "4") (pinfunction "ID_4") (pintype "passive+no_connect"))
    )
    (net (code "27") (name "GND") (class "Default")
      (node (ref "C1") (pin "2") (pinfunction "2_2") (pintype "passive"))
      (node (ref "C11") (pin "2") (pinfunction "2_2") (pintype "passive"))
      (node (ref "C12") (pin "2") (pinfunction "2_2") (pintype "passive"))
      (node (ref "C13") (pin "2") (pinfunction "2_2") (pintype "passive"))
      (node (ref "C14") (pin "2") (pinfunction "2_2") (pintype "passive"))
      (node (ref "C15") (pin "2") (pinfunction "2_2") (pintype "passive"))
      (node (ref "C16") (pin "2") (pinfunction "2_2") (pintype "passive"))
      (node (ref "C17") (pin "2") (pinfunction "2_2") (pintype "passive"))
      (node (ref "C19") (pin "2") (pinfunction "2_2") (pintype "passive"))
      (node (ref "C2") (pin "2") (pinfunction "2_2") (pintype "passive"))
      (node (ref "C22") (pin "1") (pinfunction "1_1") (pintype "passive"))
      (node (ref "C23") (pin "1") (pinfunction "1_1") (pintype "passive"))
      (node (ref "C24") (pin "1") (pinfunction "1_1") (pintype "passive"))
      (node (ref "C25") (pin "1") (pinfunction "1_1") (pintype "passive"))
      (node (ref "C3") (pin "2") (pinfunction "2_2") (pintype "passive"))
      (node (ref "C4") (pin "2") (pinfunction "2_2") (pintype "passive"))
      (node (ref "C5") (pin "2") (pinfunction "2_2") (pintype "passive"))
      (node (ref "C7") (pin "2") (pinfunction "2_2") (pintype "passive"))
      (node (ref "C8") (pin "2") (pinfunction "2_2") (pintype "passive"))
      (node (ref "C9") (pin "2") (pinfunction "2_2") (pintype "passive"))
      (node (ref "D1") (pin "K") (pinfunction "K_K") (pintype "passive"))
      (node (ref "D6") (pin "K") (pinfunction "K_K") (pintype "passive"))
      (node (ref "L2") (pin "1") (pinfunction "1_1") (pintype "passive"))
      (node (ref "P1") (pin "5") (pinfunction "GND_5") (pintype "power_in"))
      (node (ref "P1") (pin "6") (pinfunction "SHIELD_6") (pintype "passive"))
      (node (ref "P2") (pin "2") (pinfunction "2_2") (pintype "passive"))
      (node (ref "P2") (pin "4") (pinfunction "4_4") (pintype "passive"))
      (node (ref "P3") (pin "10") (pinfunction "10_10") (pintype "passive"))
      (node (ref "P3") (pin "2") (pinfunction "2_2") (pintype "passive"))
      (node (ref "P3") (pin "4") (pinfunction "4_4") (pintype "passive"))
      (node (ref "P3") (pin "6") (pinfunction "6_6") (pintype "passive"))
      (node (ref "P3") (pin "8") (pinfunction "8_8") (pintype "passive"))
      (node (ref "P4") (pin "10") (pinfunction "10_10") (pintype "passive"))
      (node (ref "P4") (pin "2") (pinfunction "2_2") (pintype "passive"))
      (node (ref "P4") (pin "4") (pinfunction "4_4") (pintype "passive"))
      (node (ref "P4") (pin "6") (pinfunction "6_6") (pintype "passive"))
      (node (ref "P4") (pin "8") (pinfunction "8_8") (pintype "passive"))
      (node (ref "P5") (pin "3") (pinfunction "3_3") (pintype "passive"))
      (node (ref "P5") (pin "4") (pinfunction "4_4") (pintype "passive"))
      (node (ref "P6") (pin "1") (pinfunction "1_1") (pintype "passive"))
      (node (ref "P6") (pin "2") (pinfunction "2_2") (pintype "passive"))
      (node (ref "Q4") (pin "2") (pinfunction "S_2") (pintype "passive"))
      (node (ref "R11") (pin "2") (pinfunction "2_2") (pintype "passive"))
      (node (ref "R14") (pin "1") (pinfunction "1_1") (pintype "passive"))
      (node (ref "R15") (pin "2") (pinfunction "2_2") (pintype "passive"))
      (node (ref "R23") (pin "2") (pinfunction "2_2") (pintype "passive"))
      (node (ref "R23") (pin "3") (pinfunction "3_3") (pintype "passive"))
      (node (ref "R23") (pin "4") (pinfunction "MH_4") (pintype "passive"))
      (node (ref "R23") (pin "5") (pinfunction "MH_5") (pintype "passive"))
      (node (ref "R24") (pin "2") (pinfunction "2_2") (pintype "passive"))
      (node (ref "R29") (pin "2") (pinfunction "2_2") (pintype "passive"))
      (node (ref "R33") (pin "1") (pinfunction "1_1") (pintype "passive"))
      (node (ref "R8") (pin "1") (pinfunction "1_1") (pintype "passive"))
      (node (ref "R8") (pin "2") (pinfunction "2_2") (pintype "passive"))
      (node (ref "R8") (pin "4") (pinfunction "MH_4") (pintype "passive"))
      (node (ref "R8") (pin "5") (pinfunction "MH_5") (pintype "passive"))
      (node (ref "S1") (pin "EH") (pinfunction "MH_EH") (pintype "passive"))
      (node (ref "TP11") (pin "1") (pinfunction "1_1") (pintype "passive"))
      (node (ref "U2") (pin "2") (pinfunction "SWE_2") (pintype "passive"))
      (node (ref "U2") (pin "4") (pinfunction "GND_4") (pintype "power_in"))
    )
    (net (code "28") (name "Net-(D4-PadA)") (class "Default")
      (node (ref "D4") (pin "A") (pinfunction "A_A") (pintype "passive"))
      (node (ref "R6") (pin "1") (pinfunction "1_1") (pintype "passive"))
    )
    (net (code "29") (name "Net-(D6-PadA)") (class "Default")
      (node (ref "D6") (pin "A") (pinfunction "A_A") (pintype "passive"))
      (node (ref "R27") (pin "2") (pinfunction "2_2") (pintype "passive"))
    )
    (net (code "30") (name "Net-(Q2-D)") (class "Default")
      (node (ref "Q2") (pin "3") (pinfunction "D_3") (pintype "passive"))
      (node (ref "Q4") (pin "1") (pinfunction "G_1") (pintype "passive"))
      (node (ref "R14") (pin "2") (pinfunction "2_2") (pintype "passive"))
    )
    (net (code "31") (name "Net-(Q2-G)") (class "Default")
      (node (ref "Q2") (pin "1") (pinfunction "G_1") (pintype "passive"))
      (node (ref "R5") (pin "2") (pinfunction "2_2") (pintype "passive"))
    )
    (net (code "32") (name "Net-(Q3-G)") (class "Default")
      (node (ref "Q3") (pin "1") (pinfunction "G_1") (pintype "passive"))
      (node (ref "R12") (pin "2") (pinfunction "2_2") (pintype "passive"))
    )
    (net (code "33") (name "Net-(Q4-D)") (class "Default")
      (node (ref "D4") (pin "K") (pinfunction "K_K") (pintype "passive"))
      (node (ref "Q4") (pin "3") (pinfunction "D_3") (pintype "passive"))
    )
    (net (code "34") (name "Net-(Q5-B)") (class "Default")
      (node (ref "C10") (pin "1") (pinfunction "1_1") (pintype "passive"))
      (node (ref "Q5") (pin "1") (pinfunction "B_1") (pintype "passive"))
      (node (ref "R16") (pin "1") (pinfunction "1_1") (pintype "passive"))
      (node (ref "R9") (pin "2") (pinfunction "2_2") (pintype "passive"))
    )
    (net (code "35") (name "Net-(Q5-C)") (class "Default")
      (node (ref "C10") (pin "2") (pinfunction "2_2") (pintype "passive"))
      (node (ref "C6") (pin "2") (pinfunction "2_2") (pintype "passive"))
      (node (ref "Q5") (pin "3") (pinfunction "C_3") (pintype "passive"))
      (node (ref "R10") (pin "2") (pinfunction "2_2") (pintype "passive"))
      (node (ref "R12") (pin "1") (pinfunction "1_1") (pintype "passive"))
    )
    (net (code "36") (name "Net-(Q6-D)") (class "Default")
      (node (ref "Q6") (pin "3") (pinfunction "D_3") (pintype "passive"))
      (node (ref "R21") (pin "1") (pinfunction "1_1") (pintype "passive"))
    )
    (net (code "37") (name "Net-(Q6-G)") (class "Default")
      (node (ref "Q6") (pin "1") (pinfunction "G_1") (pintype "passive"))
      (node (ref "R19") (pin "2") (pinfunction "2_2") (pintype "passive"))
    )
    (net (code "38") (name "Net-(Q7-D)") (class "Default")
      (node (ref "Q7") (pin "3") (pinfunction "D_3") (pintype "passive"))
      (node (ref "R27") (pin "1") (pinfunction "1_1") (pintype "passive"))
    )
    (net (code "39") (name "Net-(Q7-G)") (class "Default")
      (node (ref "Q7") (pin "1") (pinfunction "G_1") (pintype "passive"))
      (node (ref "R21") (pin "2") (pinfunction "2_2") (pintype "passive"))
      (node (ref "R22") (pin "1") (pinfunction "1_1") (pintype "passive"))
    )
    (net (code "40") (name "Net-(Q8-D)") (class "Default")
      (node (ref "Q8") (pin "3") (pinfunction "D_3") (pintype "passive"))
      (node (ref "R31") (pin "1") (pinfunction "1_1") (pintype "passive"))
    )
    (net (code "41") (name "Net-(Q8-G)") (class "Default")
      (node (ref "Q8") (pin "1") (pinfunction "G_1") (pintype "passive"))
      (node (ref "R30") (pin "2") (pinfunction "2_2") (pintype "passive"))
    )
    (net (code "42") (name "Net-(Q9-B)") (class "Default")
      (node (ref "C21") (pin "1") (pinfunction "1_1") (pintype "passive"))
      (node (ref "Q9") (pin "1") (pinfunction "B_1") (pintype "passive"))
      (node (ref "R25") (pin "2") (pinfunction "2_2") (pintype "passive"))
      (node (ref "R32") (pin "1") (pinfunction "1_1") (pintype "passive"))
    )
    (net (code "43") (name "Net-(Q9-C)") (class "Default")
      (node (ref "C20") (pin "2") (pinfunction "2_2") (pintype "passive"))
      (node (ref "C21") (pin "2") (pinfunction "2_2") (pintype "passive"))
      (node (ref "Q9") (pin "3") (pinfunction "C_3") (pintype "passive"))
      (node (ref "R26") (pin "2") (pinfunction "2_2") (pintype "passive"))
      (node (ref "R30") (pin "1") (pinfunction "1_1") (pintype "passive"))
    )
    (net (code "44") (name "Net-(R33-Pad2)") (class "Default")
      (node (ref "R33") (pin "2") (pinfunction "2_2") (pintype "passive"))
      (node (ref "S1") (pin "1") (pinfunction "1_1") (pintype "passive"))
    )
    (net (code "45") (name "Net-(U2-TIMC)") (class "Default")
      (node (ref "C9") (pin "1") (pinfunction "1_1") (pintype "passive"))
      (node (ref "TP6") (pin "1") (pinfunction "1_1") (pintype "passive"))
      (node (ref "U2") (pin "3") (pinfunction "TIMC_3") (pintype "passive"))
    )
    (net (code "46") (name "Net-(U4-TIMC)") (class "Default")
      (node (ref "C18") (pin "1") (pinfunction "1_1") (pintype "passive"))
      (node (ref "TP10") (pin "1") (pinfunction "1_1") (pintype "passive"))
      (node (ref "U4") (pin "3") (pinfunction "TIMC_3") (pintype "passive"))
    )
    (net (code "47") (name "PN_VREG_S0") (class "Default")
      (node (ref "C15") (pin "1") (pinfunction "1_1") (pintype "passive"))
      (node (ref "P2") (pin "5") (pinfunction "5_5") (pintype "passive"))
      (node (ref "P4") (pin "1") (pinfunction "1_1") (pintype "passive"))
      (node (ref "P4") (pin "3") (pinfunction "3_3") (pintype "passive"))
      (node (ref "P4") (pin "5") (pinfunction "5_5") (pintype "passive"))
      (node (ref "P4") (pin "7") (pinfunction "7_7") (pintype "passive"))
      (node (ref "P4") (pin "9") (pinfunction "9_9") (pintype "passive"))
      (node (ref "P6") (pin "3") (pinfunction "3_3") (pintype "passive"))
      (node (ref "P6") (pin "4") (pinfunction "4_4") (pintype "passive"))
      (node (ref "Q6") (pin "2") (pinfunction "S_2") (pintype "passive"))
      (node (ref "R18") (pin "1") (pinfunction "1_1") (pintype "passive"))
      (node (ref "R25") (pin "1") (pinfunction "1_1") (pintype "passive"))
      (node (ref "TP8") (pin "1") (pinfunction "1_1") (pintype "passive"))
      (node (ref "U3") (pin "1") (pinfunction "VOUT_1") (pintype "power_in"))
    )
    (net (code "48") (name "PN_VTRACK_S0") (class "Default")
      (node (ref "C16") (pin "1") (pinfunction "1_1") (pintype "passive"))
      (node (ref "C18") (pin "2") (pinfunction "2_2") (pintype "passive"))
      (node (ref "C20") (pin "1") (pinfunction "1_1") (pintype "passive"))
      (node (ref "C22") (pin "2") (pinfunction "2_2") (pintype "passive"))
      (node (ref "C23") (pin "2") (pinfunction "2_2") (pintype "passive"))
      (node (ref "C24") (pin "2") (pinfunction "2_2") (pintype "passive"))
      (node (ref "C25") (pin "2") (pinfunction "2_2") (pintype "passive"))
      (node (ref "D5") (pin "2") (pinfunction "A_2") (pintype "passive"))
      (node (ref "Q8") (pin "2") (pinfunction "S_2") (pintype "passive"))
      (node (ref "Q9") (pin "2") (pinfunction "E_2") (pintype "passive"))
      (node (ref "R26") (pin "1") (pinfunction "1_1") (pintype "passive"))
      (node (ref "R28") (pin "2") (pinfunction "2_2") (pintype "passive"))
      (node (ref "R32") (pin "2") (pinfunction "2_2") (pintype "passive"))
      (node (ref "TP7") (pin "1") (pinfunction "1_1") (pintype "passive"))
      (node (ref "U3") (pin "2") (pinfunction "VIN_2") (pintype "power_in"))
      (node (ref "U3") (pin "3") (pinfunction "VIN_3") (pintype "power_in"))
      (node (ref "U3") (pin "6") (pinfunction "VIN_6") (pintype "power_in"))
      (node (ref "U3") (pin "7") (pinfunction "VIN_7") (pintype "power_in"))
      (node (ref "U4") (pin "4") (pinfunction "GND_4") (pintype "power_in"))
    )
    (net (code "49") (name "PP5V0_S0") (class "Default")
      (node (ref "C2") (pin "1") (pinfunction "1_1") (pintype "passive"))
      (node (ref "C3") (pin "1") (pinfunction "1_1") (pintype "passive"))
      (node (ref "P2") (pin "3") (pinfunction "3_3") (pintype "passive"))
      (node (ref "Q1") (pin "3") (pinfunction "D_3") (pintype "passive"))
      (node (ref "Q7") (pin "2") (pinfunction "S_2") (pintype "passive"))
      (node (ref "R1") (pin "1") (pinfunction "1_1") (pintype "passive"))
      (node (ref "R20") (pin "2") (pinfunction "2_2") (pintype "passive"))
      (node (ref "R22") (pin "2") (pinfunction "2_2") (pintype "passive"))
      (node (ref "R6") (pin "2") (pinfunction "2_2") (pintype "passive"))
      (node (ref "R7") (pin "2") (pinfunction "2_2") (pintype "passive"))
      (node (ref "XW2") (pin "2") (pinfunction "2_2") (pintype "passive"))
      (node (ref "XW4") (pin "2") (pinfunction "2_2") (pintype "passive"))
    )
    (net (code "50") (name "PP_VREG_S0") (class "Default")
      (node (ref "C5") (pin "1") (pinfunction "1_1") (pintype "passive"))
      (node (ref "P2") (pin "1") (pinfunction "1_1") (pintype "passive"))
      (node (ref "P3") (pin "1") (pinfunction "1_1") (pintype "passive"))
      (node (ref "P3") (pin "3") (pinfunction "3_3") (pintype "passive"))
      (node (ref "P3") (pin "5") (pinfunction "5_5") (pintype "passive"))
      (node (ref "P3") (pin "7") (pinfunction "7_7") (pintype "passive"))
      (node (ref "P3") (pin "9") (pinfunction "9_9") (pintype "passive"))
      (node (ref "P5") (pin "1") (pinfunction "1_1") (pintype "passive"))
      (node (ref "P5") (pin "2") (pinfunction "2_2") (pintype "passive"))
      (node (ref "Q2") (pin "2") (pinfunction "S_2") (pintype "passive"))
      (node (ref "Q5") (pin "2") (pinfunction "E_2") (pintype "passive"))
      (node (ref "R16") (pin "2") (pinfunction "2_2") (pintype "passive"))
      (node (ref "R3") (pin "1") (pinfunction "1_1") (pintype "passive"))
      (node (ref "TP5") (pin "1") (pinfunction "1_1") (pintype "passive"))
      (node (ref "U1") (pin "2") (pinfunction "VOUT_2") (pintype "power_in"))
      (node (ref "U1") (pin "3") (pinfunction "VOUT_3") (pintype "power_in"))
      (node (ref "U1") (pin "6") (pinfunction "VOUT_6") (pintype "power_in"))
      (node (ref "U1") (pin "7") (pinfunction "VOUT_7") (pintype "power_in"))
    )
    (net (code "51") (name "PP_VTRACK_S0") (class "Default")
      (node (ref "C11") (pin "1") (pinfunction "1_1") (pintype "passive"))
      (node (ref "C12") (pin "1") (pinfunction "1_1") (pintype "passive"))
      (node (ref "C13") (pin "1") (pinfunction "1_1") (pintype "passive"))
      (node (ref "C14") (pin "1") (pinfunction "1_1") (pintype "passive"))
      (node (ref "C4") (pin "1") (pinfunction "1_1") (pintype "passive"))
      (node (ref "C6") (pin "1") (pinfunction "1_1") (pintype "passive"))
      (node (ref "D2") (pin "1") (pinfunction "K_1") (pintype "passive"))
      (node (ref "D3") (pin "1") (pinfunction "K_1") (pintype "passive"))
      (node (ref "Q3") (pin "2") (pinfunction "S_2") (pintype "passive"))
      (node (ref "R10") (pin "1") (pinfunction "1_1") (pintype "passive"))
      (node (ref "R13") (pin "2") (pinfunction "2_2") (pintype "passive"))
      (node (ref "R9") (pin "1") (pinfunction "1_1") (pintype "passive"))
      (node (ref "TP4") (pin "1") (pinfunction "1_1") (pintype "passive"))
      (node (ref "U1") (pin "1") (pinfunction "VIN_1") (pintype "power_in"))
    )
  )
)
